# ProPrj_New_Project_2026-03-26_23-50-09_2.net
KiCad netlist of a schematic drawn in EasyEDA Pro
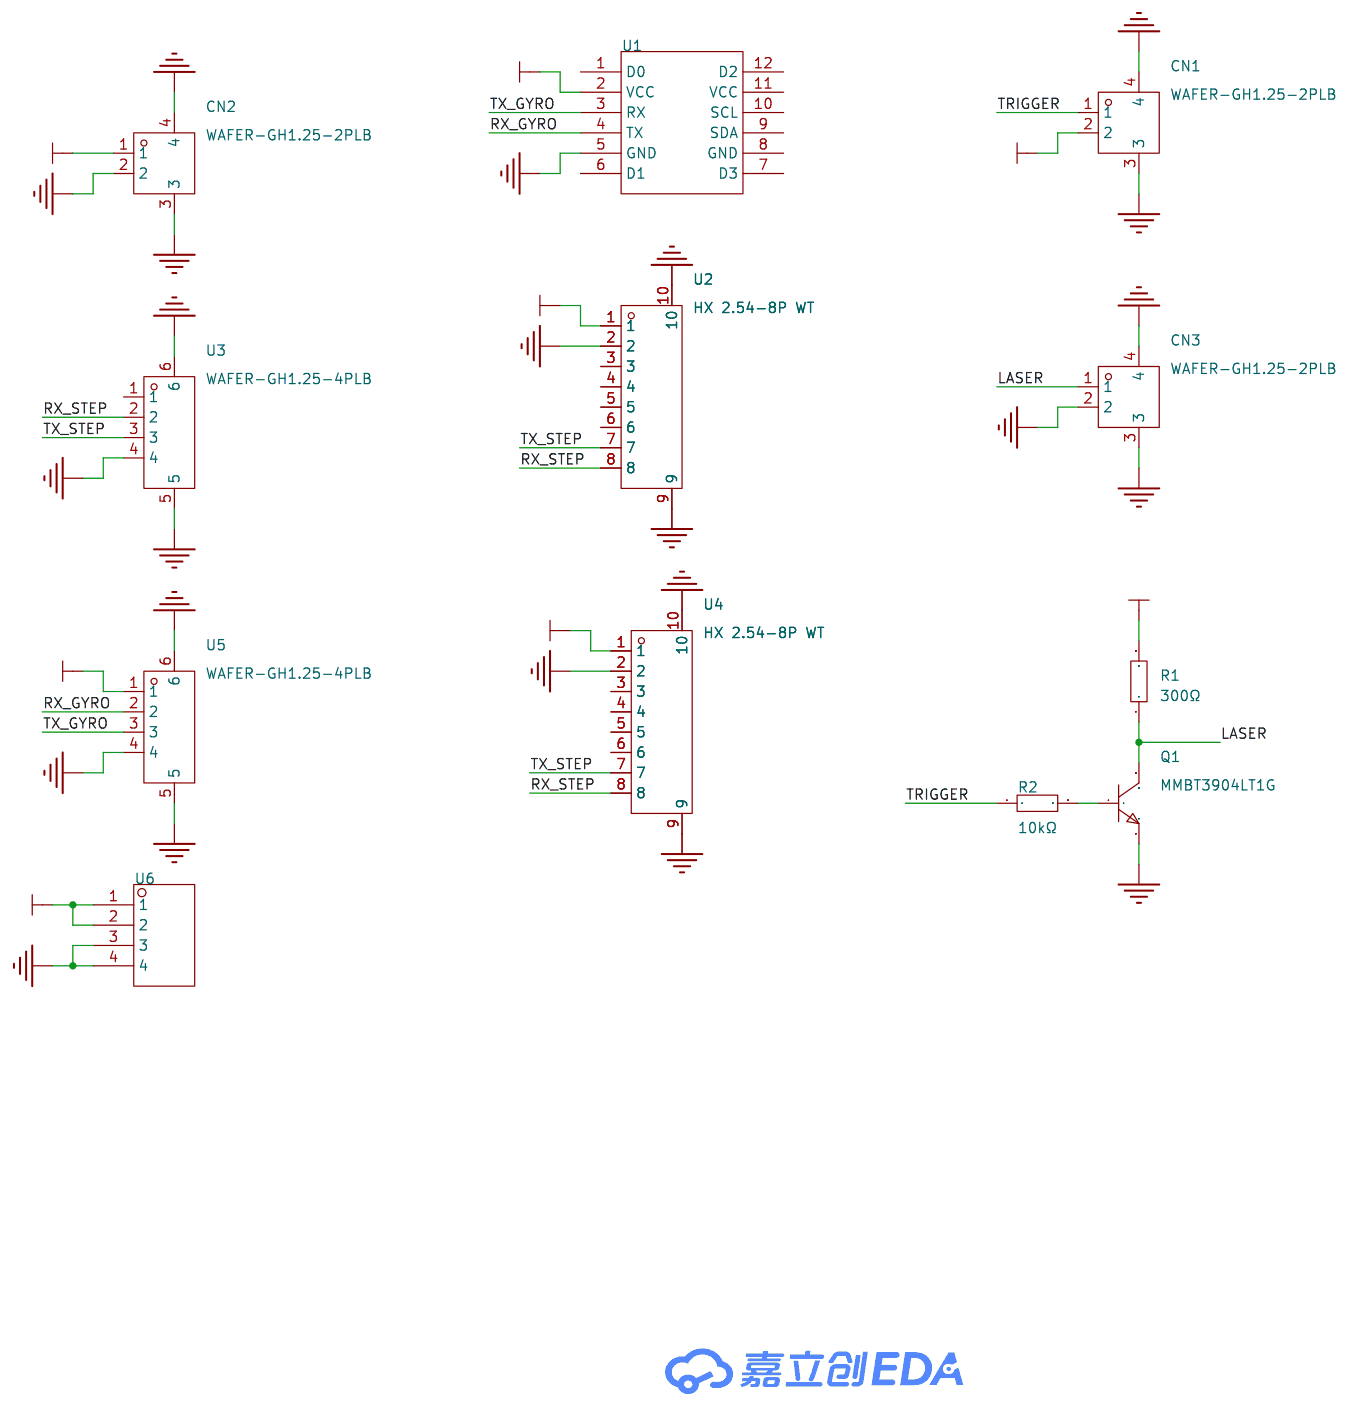
[diagram p0: schematic sheet]

(export (version "E")
  (design (tool "Eeschema 10.0.6"))
  (components
    (comp (ref "CN1")
      (value "WAFER-GH1.25-2PLB")
      (footprint "easyedapro:CONN-TH_2P-P1.25_XUNPU_WAFER-GH1.25-2PLB")
      (fields (field (name "Manufacturer") "XUNPU(讯普)"))
      (libsource (lib "easyedapro") (part "WAFER-GH1.25-2PLB"))
    )
    (comp (ref "CN2")
      (value "WAFER-GH1.25-2PLB")
      (footprint "easyedapro:CONN-TH_2P-P1.25_XUNPU_WAFER-GH1.25-2PLB")
      (fields (field (name "Manufacturer") "XUNPU(讯普)"))
      (libsource (lib "easyedapro") (part "WAFER-GH1.25-2PLB"))
    )
    (comp (ref "CN3")
      (value "WAFER-GH1.25-2PLB")
      (footprint "easyedapro:CONN-TH_2P-P1.25_XUNPU_WAFER-GH1.25-2PLB")
      (fields (field (name "Manufacturer") "XUNPU(讯普)"))
      (libsource (lib "easyedapro") (part "WAFER-GH1.25-2PLB"))
    )
    (comp (ref "Q1")
      (value "MMBT3904LT1G")
      (footprint "easyedapro:SOT-23-3_L2.9-W1.6-P1.90-LS2.8-BR")
      (description "晶体管类型:NPN;集电极电流(Ic):200mA;集射极击穿电压(Vceo):40V;耗散功率(Pd):225mW;直流电流增益(hFE):40@0.1mA,1.0V;")
      (fields (field (name "Manufacturer") "onsemi(安森美)"))
      (libsource (lib "easyedapro") (part "MMBT3904LT1G"))
    )
    (comp (ref "R1")
      (value "300Ω")
      (footprint "easyedapro:R0603")
      (description "电阻类型:厚膜电阻;阻值:300Ω;精度:±1%;功率:100mW;工作电压:75V;温度系数:±100ppm/°C;")
      (fields
        (field (name "Manufacturer Part") "0603WAF3000T5E")
        (field (name "Manufacturer") "UNI-ROYAL(厚声)")
      )
      (libsource (lib "easyedapro") (part "0603WAF3000T5E"))
    )
    (comp (ref "R2")
      (value "10kΩ")
      (footprint "easyedapro:R0603")
      (description "电阻类型:厚膜电阻;阻值:10kΩ;精度:±1%;功率:100mW;最大工作电压:75V;温度系数:±100ppm/°C;")
      (fields (field (name "Manufacturer Part") "RC0603FR-0710KL") (field (name "Manufacturer") "YAGEO(国巨)"))
      (libsource (lib "easyedapro") (part "RC0603FR-0710KL"))
    )
    (comp (ref "U1") (value "~") (footprint "easyedapro:JY61P") (libsource (lib "easyedapro") (part "JY61P")))
    (comp (ref "U2")
      (value "HX 2.54-8P WT")
      (footprint "easyedapro:CONN-SMD_8P-P2.50_HANXIA_HX-2.54-8P-WTDK")
      (description "插针结构:1x8P;间距:2.54mm;安装方式:卧贴;参考系列:XH;总PIN数:8P;排数:1;每排PIN数:8;额定电流:3A;工作温度范围:-25°C~+85°C;")
      (fields (field (name "Manufacturer") "hanxia(韩下)"))
      (libsource (lib "easyedapro") (part "HX 2.54-8P WT"))
    )
    (comp (ref "U3")
      (value "WAFER-GH1.25-4PLB")
      (footprint "easyedapro:CONN-SMD_4P-P1.25_XUNPU_WAFER-GH1.25-4PLB")
      (fields (field (name "Manufacturer") "XUNPU(讯普)"))
      (libsource (lib "easyedapro") (part "WAFER-GH1.25-4PLB"))
    )
    (comp (ref "U4")
      (value "HX 2.54-8P WT")
      (footprint "easyedapro:CONN-SMD_8P-P2.50_HANXIA_HX-2.54-8P-WTDK")
      (description "插针结构:1x8P;间距:2.54mm;安装方式:卧贴;参考系列:XH;总PIN数:8P;排数:1;每排PIN数:8;额定电流:3A;工作温度范围:-25°C~+85°C;")
      (fields (field (name "Manufacturer") "hanxia(韩下)"))
      (libsource (lib "easyedapro") (part "HX 2.54-8P WT"))
    )
    (comp (ref "U5")
      (value "WAFER-GH1.25-4PLB")
      (footprint "easyedapro:CONN-SMD_4P-P1.25_XUNPU_WAFER-GH1.25-4PLB")
      (fields (field (name "Manufacturer") "XUNPU(讯普)"))
      (libsource (lib "easyedapro") (part "WAFER-GH1.25-4PLB"))
    )
    (comp (ref "U6")
      (value "~")
      (footprint "easyedapro:Slip Ring")
      (libsource (lib "easyedapro") (part "Slip Ring"))
    )
  )
  (nets
    (net (code "1") (name "+5V") (class "Default")
      (node (ref "U1") (pin "2") (pinfunction "VCC_2") (pintype "input"))
      (node (ref "U5") (pin "1") (pinfunction "1_1") (pintype "unspecified"))
    )
    (net (code "2") (name "+12V") (class "Default")
      (node (ref "CN2") (pin "1") (pinfunction "1_1") (pintype "unspecified"))
      (node (ref "U2") (pin "1") (pinfunction "1_1") (pintype "unspecified"))
      (node (ref "U4") (pin "1") (pinfunction "1_1") (pintype "unspecified"))
      (node (ref "U6") (pin "1") (pinfunction "1_1") (pintype "input"))
      (node (ref "U6") (pin "2") (pinfunction "2_2") (pintype "input"))
    )
    (net (code "3") (name "/LASER") (class "Default")
      (node (ref "CN3") (pin "1") (pinfunction "1_1") (pintype "unspecified"))
      (node (ref "Q1") (pin "3") (pinfunction "3_3") (pintype "input"))
      (node (ref "R1") (pin "1") (pinfunction "1_1") (pintype "input"))
    )
    (net (code "4") (name "/RX_GYRO") (class "Default")
      (node (ref "U1") (pin "4") (pinfunction "TX_4") (pintype "input"))
      (node (ref "U5") (pin "2") (pinfunction "2_2") (pintype "unspecified"))
    )
    (net (code "5") (name "/RX_STEP") (class "Default")
      (node (ref "U2") (pin "8") (pinfunction "8_8") (pintype "unspecified"))
      (node (ref "U3") (pin "2") (pinfunction "2_2") (pintype "unspecified"))
      (node (ref "U4") (pin "8") (pinfunction "8_8") (pintype "unspecified"))
    )
    (net (code "6") (name "/TRIGGER") (class "Default")
      (node (ref "CN1") (pin "1") (pinfunction "1_1") (pintype "unspecified"))
      (node (ref "R2") (pin "1") (pinfunction "1_1") (pintype "input"))
    )
    (net (code "7") (name "/TX_GYRO") (class "Default")
      (node (ref "U1") (pin "3") (pinfunction "RX_3") (pintype "input"))
      (node (ref "U5") (pin "3") (pinfunction "3_3") (pintype "unspecified"))
    )
    (net (code "8") (name "/TX_STEP") (class "Default")
      (node (ref "U2") (pin "7") (pinfunction "7_7") (pintype "unspecified"))
      (node (ref "U3") (pin "3") (pinfunction "3_3") (pintype "unspecified"))
      (node (ref "U4") (pin "7") (pinfunction "7_7") (pintype "unspecified"))
    )
    (net (code "9") (name "GND") (class "Default")
      (node (ref "CN1") (pin "3") (pinfunction "3_3") (pintype "unspecified"))
      (node (ref "CN1") (pin "4") (pinfunction "4_4") (pintype "unspecified"))
      (node (ref "CN2") (pin "2") (pinfunction "2_2") (pintype "unspecified"))
      (node (ref "CN2") (pin "3") (pinfunction "3_3") (pintype "unspecified"))
      (node (ref "CN2") (pin "4") (pinfunction "4_4") (pintype "unspecified"))
      (node (ref "CN3") (pin "2") (pinfunction "2_2") (pintype "unspecified"))
      (node (ref "CN3") (pin "3") (pinfunction "3_3") (pintype "unspecified"))
      (node (ref "CN3") (pin "4") (pinfunction "4_4") (pintype "unspecified"))
      (node (ref "Q1") (pin "2") (pinfunction "2_2") (pintype "input"))
      (node (ref "U1") (pin "5") (pinfunction "GND_5") (pintype "input"))
      (node (ref "U2") (pin "10") (pinfunction "10_10") (pintype "unspecified"))
      (node (ref "U2") (pin "2") (pinfunction "2_2") (pintype "unspecified"))
      (node (ref "U2") (pin "9") (pinfunction "9_9") (pintype "unspecified"))
      (node (ref "U3") (pin "4") (pinfunction "4_4") (pintype "unspecified"))
      (node (ref "U3") (pin "5") (pinfunction "5_5") (pintype "unspecified"))
      (node (ref "U3") (pin "6") (pinfunction "6_6") (pintype "unspecified"))
      (node (ref "U4") (pin "10") (pinfunction "10_10") (pintype "unspecified"))
      (node (ref "U4") (pin "2") (pinfunction "2_2") (pintype "unspecified"))
      (node (ref "U4") (pin "9") (pinfunction "9_9") (pintype "unspecified"))
      (node (ref "U5") (pin "4") (pinfunction "4_4") (pintype "unspecified"))
      (node (ref "U5") (pin "5") (pinfunction "5_5") (pintype "unspecified"))
      (node (ref "U5") (pin "6") (pinfunction "6_6") (pintype "unspecified"))
      (node (ref "U6") (pin "3") (pinfunction "3_3") (pintype "input"))
      (node (ref "U6") (pin "4") (pinfunction "4_4") (pintype "input"))
    )
    (net (code "10") (name "LPWR") (class "Default")
      (node (ref "CN1") (pin "2") (pinfunction "2_2") (pintype "unspecified"))
      (node (ref "R1") (pin "2") (pinfunction "2_2") (pintype "input"))
    )
    (net (code "11") (name "Net-(Q1-Pad1)") (class "Default")
      (node (ref "Q1") (pin "1") (pinfunction "1_1") (pintype "input"))
      (node (ref "R2") (pin "2") (pinfunction "2_2") (pintype "input"))
    )
    (net (code "12") (name "unconnected-(U1-D0-Pad1)") (class "Default")
      (node (ref "U1") (pin "1") (pinfunction "D0_1") (pintype "input"))
    )
    (net (code "13") (name "unconnected-(U1-D1-Pad6)") (class "Default")
      (node (ref "U1") (pin "6") (pinfunction "D1_6") (pintype "input"))
    )
    (net (code "14") (name "unconnected-(U1-D2-Pad12)") (class "Default")
      (node (ref "U1") (pin "12") (pinfunction "D2_12") (pintype "input"))
    )
    (net (code "15") (name "unconnected-(U1-D3-Pad7)") (class "Default")
      (node (ref "U1") (pin "7") (pinfunction "D3_7") (pintype "input"))
    )
    (net (code "16") (name "unconnected-(U1-GND-Pad8)") (class "Default")
      (node (ref "U1") (pin "8") (pinfunction "GND_8") (pintype "input"))
    )
    (net (code "17") (name "unconnected-(U1-SCL-Pad10)") (class "Default")
      (node (ref "U1") (pin "10") (pinfunction "SCL_10") (pintype "input"))
    )
    (net (code "18") (name "unconnected-(U1-SDA-Pad9)") (class "Default")
      (node (ref "U1") (pin "9") (pinfunction "SDA_9") (pintype "input"))
    )
    (net (code "19") (name "unconnected-(U1-VCC-Pad11)") (class "Default")
      (node (ref "U1") (pin "11") (pinfunction "VCC_11") (pintype "input"))
    )
    (net (code "20") (name "unconnected-(U2-Pad3)") (class "Default")
      (node (ref "U2") (pin "3") (pinfunction "3_3") (pintype "unspecified"))
    )
    (net (code "21") (name "unconnected-(U2-Pad4)") (class "Default")
      (node (ref "U2") (pin "4") (pinfunction "4_4") (pintype "unspecified"))
    )
    (net (code "22") (name "unconnected-(U2-Pad5)") (class "Default")
      (node (ref "U2") (pin "5") (pinfunction "5_5") (pintype "unspecified"))
    )
    (net (code "23") (name "unconnected-(U2-Pad6)") (class "Default")
      (node (ref "U2") (pin "6") (pinfunction "6_6") (pintype "unspecified"))
    )
    (net (code "24") (name "unconnected-(U3-Pad1)") (class "Default")
      (node (ref "U3") (pin "1") (pinfunction "1_1") (pintype "unspecified"))
    )
    (net (code "25") (name "unconnected-(U4-Pad3)") (class "Default")
      (node (ref "U4") (pin "3") (pinfunction "3_3") (pintype "unspecified"))
    )
    (net (code "26") (name "unconnected-(U4-Pad4)") (class "Default")
      (node (ref "U4") (pin "4") (pinfunction "4_4") (pintype "unspecified"))
    )
    (net (code "27") (name "unconnected-(U4-Pad5)") (class "Default")
      (node (ref "U4") (pin "5") (pinfunction "5_5") (pintype "unspecified"))
    )
    (net (code "28") (name "unconnected-(U4-Pad6)") (class "Default")
      (node (ref "U4") (pin "6") (pinfunction "6_6") (pintype "unspecified"))
    )
  )
)
